# Color_sensor_Sensor_Board.net
KiCad netlist of a schematic drawn in EAGLE
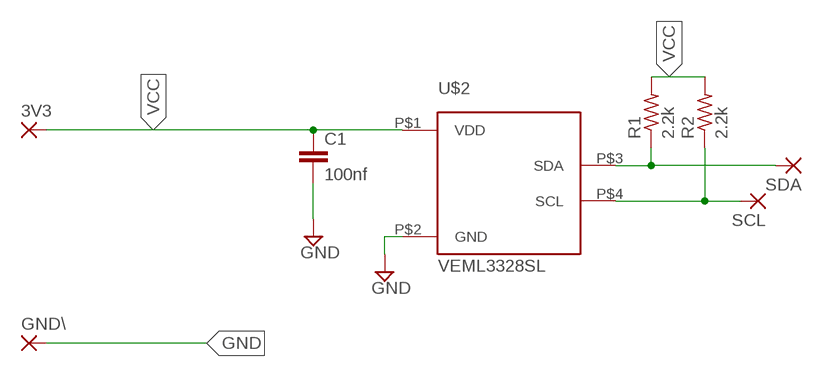
[diagram p0: schematic, sheet 1]

(export (version "E")
  (design (tool "Eeschema 10.0.6"))
  (components
    (comp (ref "3V3")
      (value "SMD2")
      (footprint "eagle-import:SMD1,27-2,54")
      (libsource (lib "eagle-import") (part "SMD2"))
    )
    (comp (ref "C1")
      (value "100nf")
      (footprint "eagle-import:C0805")
      (libsource (lib "eagle-import") (part "C-EUC0805"))
    )
    (comp (ref "GND\\")
      (value "SMD2")
      (footprint "eagle-import:SMD1,27-2,54")
      (libsource (lib "eagle-import") (part "SMD2"))
    )
    (comp (ref "R1")
      (value "2.2k")
      (footprint "eagle-import:R0805")
      (libsource (lib "eagle-import") (part "R-US_R0805"))
    )
    (comp (ref "R2")
      (value "2.2k")
      (footprint "eagle-import:R0805")
      (libsource (lib "eagle-import") (part "R-US_R0805"))
    )
    (comp (ref "SCL")
      (value "SMD2")
      (footprint "eagle-import:SMD1,27-2,54")
      (libsource (lib "eagle-import") (part "SMD2"))
    )
    (comp (ref "SDA")
      (value "SMD2")
      (footprint "eagle-import:SMD1,27-2,54")
      (libsource (lib "eagle-import") (part "SMD2"))
    )
    (comp (ref "U$2")
      (value "VEML3328SL")
      (footprint "eagle-import:OPLGA4SV")
      (libsource (lib "eagle-import") (part "VEML3328SL"))
    )
  )
  (nets
    (net (code "1") (name "GND") (class "Default")
      (node (ref "C1") (pin "2") (pinfunction "2_2") (pintype "passive"))
      (node (ref "GND\\") (pin "1") (pinfunction "P_1") (pintype "passive"))
      (node (ref "U$2") (pin "P$2") (pinfunction "GND_P$2") (pintype "power_in"))
    )
    (net (code "2") (name "Net-(SCL-P)") (class "Default")
      (node (ref "R2") (pin "1") (pinfunction "1_1") (pintype "passive"))
      (node (ref "SCL") (pin "1") (pinfunction "P_1") (pintype "passive"))
      (node (ref "U$2") (pin "P$4") (pinfunction "SCL_P$4") (pintype "bidirectional"))
    )
    (net (code "3") (name "Net-(SDA-P)") (class "Default")
      (node (ref "R1") (pin "1") (pinfunction "1_1") (pintype "passive"))
      (node (ref "SDA") (pin "1") (pinfunction "P_1") (pintype "passive"))
      (node (ref "U$2") (pin "P$3") (pinfunction "SDA_P$3") (pintype "bidirectional"))
    )
    (net (code "4") (name "VCC") (class "Default")
      (node (ref "3V3") (pin "1") (pinfunction "P_1") (pintype "passive"))
      (node (ref "C1") (pin "1") (pinfunction "1_1") (pintype "passive"))
      (node (ref "R1") (pin "2") (pinfunction "2_2") (pintype "passive"))
      (node (ref "R2") (pin "2") (pinfunction "2_2") (pintype "passive"))
      (node (ref "U$2") (pin "P$1") (pinfunction "VDD_P$1") (pintype "power_in"))
    )
  )
)
